# vacuum_sensor.net
KiCad netlist of a schematic drawn in EAGLE
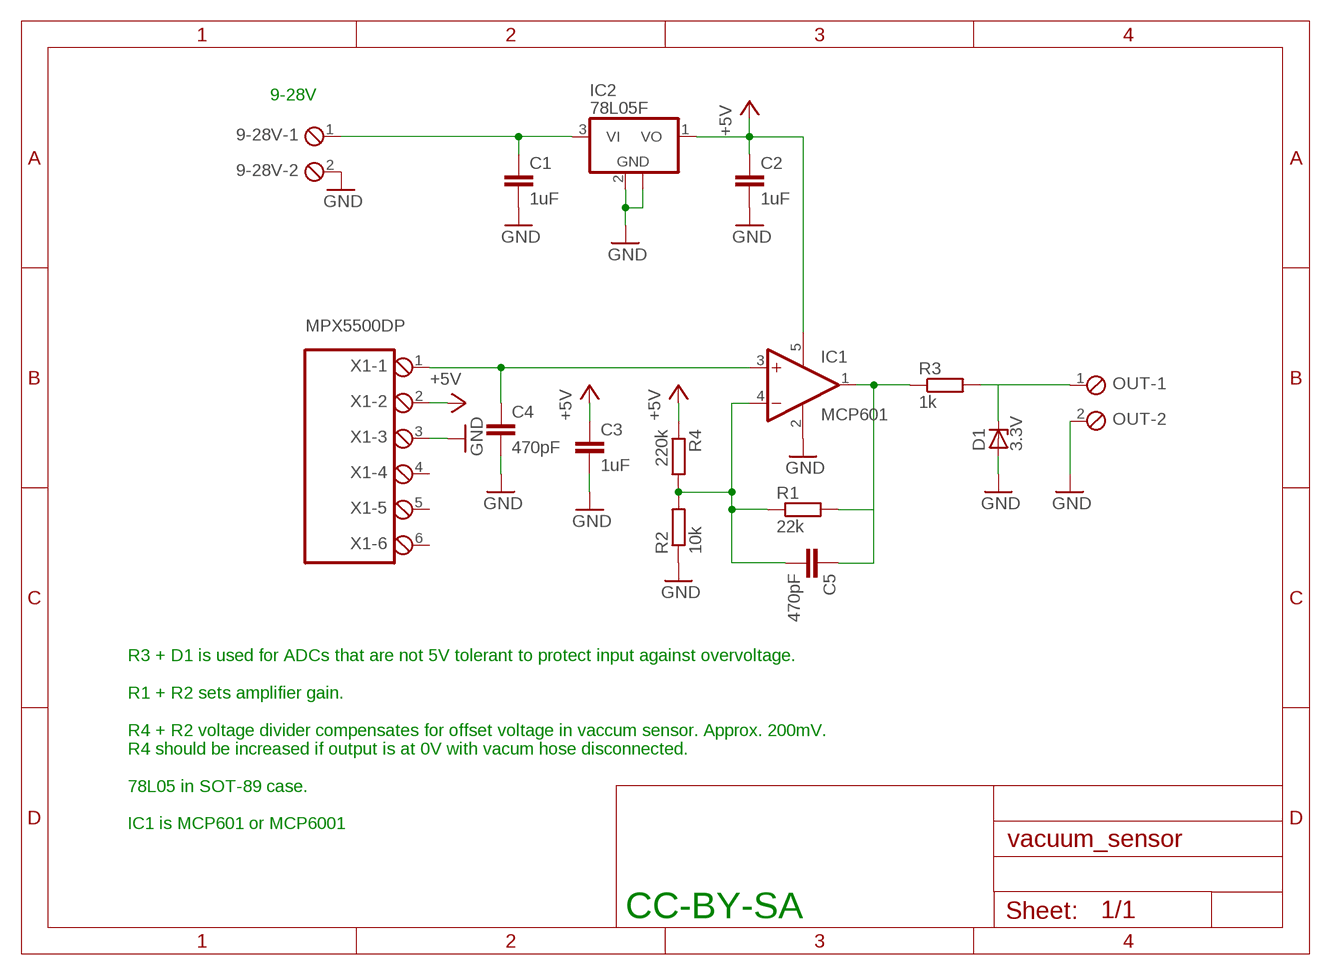
[diagram p0: schematic, sheet 1]

(export (version "E")
  (design (tool "Eeschema 10.0.6"))
  (components
    (comp (ref "9-28V")
      (value "MPT2")
      (footprint "eagle-import:2POL254")
      (libsource (lib "eagle-import") (part "MPT2"))
    )
    (comp (ref "C1")
      (value "1uF")
      (footprint "eagle-import:C0805")
      (libsource (lib "eagle-import") (part "C-EUC0805"))
    )
    (comp (ref "C2")
      (value "1uF")
      (footprint "eagle-import:C0805")
      (libsource (lib "eagle-import") (part "C-EUC0805"))
    )
    (comp (ref "C3")
      (value "1uF")
      (footprint "eagle-import:C0805")
      (libsource (lib "eagle-import") (part "C-EUC0805"))
    )
    (comp (ref "C4")
      (value "470pF")
      (footprint "eagle-import:C0805")
      (libsource (lib "eagle-import") (part "C-EUC0805"))
    )
    (comp (ref "C5")
      (value "470pF")
      (footprint "eagle-import:C0805")
      (libsource (lib "eagle-import") (part "C-EUC0805"))
    )
    (comp (ref "D1")
      (value "3.3V")
      (footprint "eagle-import:SOT23")
      (libsource (lib "eagle-import") (part "ZENER-DIODESOT23"))
    )
    (comp (ref "IC1")
      (value "MCP601")
      (footprint "eagle-import:SOT23-5")
      (libsource (lib "eagle-import") (part "MCP601OT"))
    )
    (comp (ref "IC2")
      (value "78L05F")
      (footprint "eagle-import:SOT89")
      (libsource (lib "eagle-import") (part "78LF05"))
    )
    (comp (ref "OUT")
      (value "MPT2")
      (footprint "eagle-import:2POL254")
      (libsource (lib "eagle-import") (part "MPT2"))
    )
    (comp (ref "R1")
      (value "22k")
      (footprint "eagle-import:R0805")
      (libsource (lib "eagle-import") (part "R-EU_R0805"))
    )
    (comp (ref "R2")
      (value "10k")
      (footprint "eagle-import:R0805")
      (libsource (lib "eagle-import") (part "R-EU_R0805"))
    )
    (comp (ref "R3")
      (value "1k")
      (footprint "eagle-import:R0805")
      (libsource (lib "eagle-import") (part "R-EU_R0805"))
    )
    (comp (ref "R4")
      (value "220k")
      (footprint "eagle-import:R0805")
      (libsource (lib "eagle-import") (part "R-EU_R0805"))
    )
    (comp (ref "X1")
      (value "MPT6")
      (footprint "eagle-import:6POL254")
      (libsource (lib "eagle-import") (part "MPT6"))
    )
  )
  (nets
    (net (code "1") (name "+5V") (class "Default")
      (node (ref "C2") (pin "1") (pinfunction "1_1") (pintype "passive"))
      (node (ref "C3") (pin "1") (pinfunction "1_1") (pintype "passive"))
      (node (ref "IC1") (pin "5") (pinfunction "V+_5") (pintype "power_in"))
      (node (ref "IC2") (pin "1") (pinfunction "VO_1") (pintype "passive"))
      (node (ref "R4") (pin "1") (pinfunction "1_1") (pintype "passive"))
      (node (ref "X1") (pin "2") (pinfunction "1_2") (pintype "passive"))
    )
    (net (code "2") (name "GND") (class "Default")
      (node (ref "9-28V") (pin "2") (pinfunction "1_2") (pintype "passive"))
      (node (ref "C1") (pin "2") (pinfunction "2_2") (pintype "passive"))
      (node (ref "C2") (pin "2") (pinfunction "2_2") (pintype "passive"))
      (node (ref "C3") (pin "2") (pinfunction "2_2") (pintype "passive"))
      (node (ref "C4") (pin "2") (pinfunction "2_2") (pintype "passive"))
      (node (ref "D1") (pin "1") (pinfunction "A_1") (pintype "passive"))
      (node (ref "IC1") (pin "2") (pinfunction "V-_2") (pintype "power_in"))
      (node (ref "IC2") (pin "2") (pinfunction "GND_2") (pintype "passive"))
      (node (ref "IC2") (pin "2@1") (pinfunction "GND_2@1") (pintype "passive"))
      (node (ref "OUT") (pin "2") (pinfunction "1_2") (pintype "passive"))
      (node (ref "R2") (pin "1") (pinfunction "1_1") (pintype "passive"))
      (node (ref "X1") (pin "3") (pinfunction "1_3") (pintype "passive"))
    )
    (net (code "3") (name "Net-(D1-C)") (class "Default")
      (node (ref "D1") (pin "3") (pinfunction "C_3") (pintype "passive"))
      (node (ref "OUT") (pin "1") (pinfunction "1_1") (pintype "passive"))
      (node (ref "R3") (pin "2") (pinfunction "2_2") (pintype "passive"))
    )
    (net (code "4") (name "Net-(IC1-+IN)") (class "Default")
      (node (ref "C4") (pin "1") (pinfunction "1_1") (pintype "passive"))
      (node (ref "IC1") (pin "3") (pinfunction "+IN_3") (pintype "input"))
      (node (ref "X1") (pin "1") (pinfunction "1_1") (pintype "passive"))
    )
    (net (code "5") (name "Net-(IC1--IN)") (class "Default")
      (node (ref "C5") (pin "2") (pinfunction "2_2") (pintype "passive"))
      (node (ref "IC1") (pin "4") (pinfunction "-IN_4") (pintype "input"))
      (node (ref "R1") (pin "1") (pinfunction "1_1") (pintype "passive"))
      (node (ref "R2") (pin "2") (pinfunction "2_2") (pintype "passive"))
      (node (ref "R4") (pin "2") (pinfunction "2_2") (pintype "passive"))
    )
    (net (code "6") (name "Net-(IC1-OUT)") (class "Default")
      (node (ref "C5") (pin "1") (pinfunction "1_1") (pintype "passive"))
      (node (ref "IC1") (pin "1") (pinfunction "OUT_1") (pintype "output"))
      (node (ref "R1") (pin "2") (pinfunction "2_2") (pintype "passive"))
      (node (ref "R3") (pin "1") (pinfunction "1_1") (pintype "passive"))
    )
    (net (code "7") (name "Net-(IC2-VI)") (class "Default")
      (node (ref "9-28V") (pin "1") (pinfunction "1_1") (pintype "passive"))
      (node (ref "C1") (pin "1") (pinfunction "1_1") (pintype "passive"))
      (node (ref "IC2") (pin "3") (pinfunction "VI_3") (pintype "input"))
    )
    (net (code "8") (name "unconnected-(X1D-1-Pad4)") (class "Default")
      (node (ref "X1") (pin "4") (pinfunction "1_4") (pintype "passive"))
    )
    (net (code "9") (name "unconnected-(X1E-1-Pad5)") (class "Default")
      (node (ref "X1") (pin "5") (pinfunction "1_5") (pintype "passive"))
    )
    (net (code "10") (name "unconnected-(X1F-1-Pad6)") (class "Default")
      (node (ref "X1") (pin "6") (pinfunction "1_6") (pintype "passive"))
    )
  )
)
